# slide-8Ch-Mux-Breakout-PMODIA.net
KiCad netlist of a schematic drawn in EAGLE
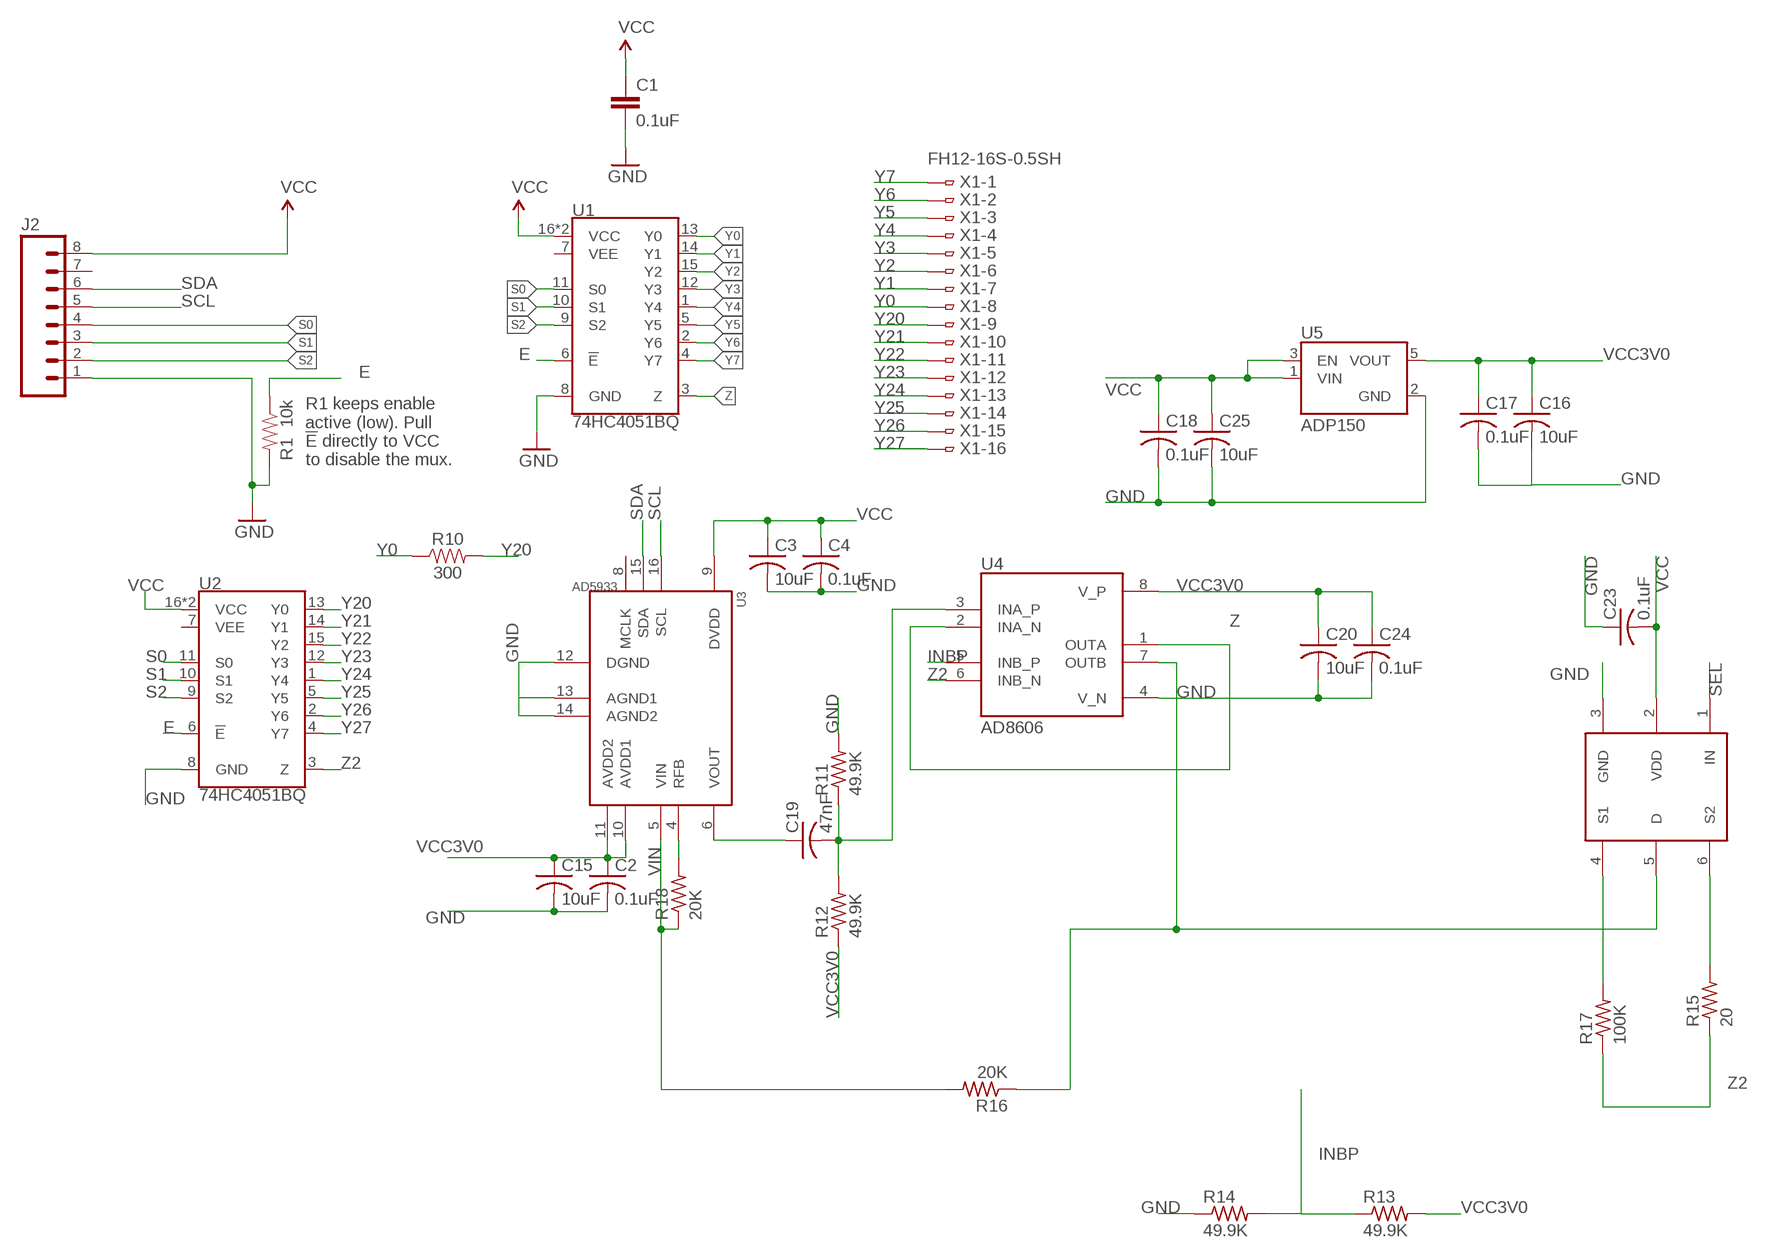
[diagram p0: schematic, sheet 1]

(export (version "E")
  (design (tool "Eeschema 10.0.6"))
  (components
    (comp (ref "C1")
      (value "0.1uF")
      (footprint "eagle-import:0603")
      (libsource (lib "eagle-import") (part "0.1UF-0603-25V-(+80/-20%)"))
    )
    (comp (ref "C2")
      (value "0.1uF")
      (footprint "eagle-import:C0805K")
      (libsource (lib "eagle-import") (part "C-USC0805K"))
    )
    (comp (ref "C3")
      (value "10uF")
      (footprint "eagle-import:C0805K")
      (libsource (lib "eagle-import") (part "C-USC0805K"))
    )
    (comp (ref "C4")
      (value "0.1uF")
      (footprint "eagle-import:C0805K")
      (libsource (lib "eagle-import") (part "C-USC0805K"))
    )
    (comp (ref "C15")
      (value "10uF")
      (footprint "eagle-import:C0805K")
      (libsource (lib "eagle-import") (part "C-USC0805K"))
    )
    (comp (ref "C16")
      (value "10uF")
      (footprint "eagle-import:C0805K")
      (libsource (lib "eagle-import") (part "C-USC0805K"))
    )
    (comp (ref "C17")
      (value "0.1uF")
      (footprint "eagle-import:C0805K")
      (libsource (lib "eagle-import") (part "C-USC0805K"))
    )
    (comp (ref "C18")
      (value "0.1uF")
      (footprint "eagle-import:C0805K")
      (libsource (lib "eagle-import") (part "C-USC0805K"))
    )
    (comp (ref "C19")
      (value "47nF")
      (footprint "eagle-import:C0805K")
      (libsource (lib "eagle-import") (part "C-USC0805K"))
    )
    (comp (ref "C20")
      (value "10uF")
      (footprint "eagle-import:C0805K")
      (libsource (lib "eagle-import") (part "C-USC0805K"))
    )
    (comp (ref "C23")
      (value "0.1uF")
      (footprint "eagle-import:C0805K")
      (libsource (lib "eagle-import") (part "C-USC0805K"))
    )
    (comp (ref "C24")
      (value "0.1uF")
      (footprint "eagle-import:C0805K")
      (libsource (lib "eagle-import") (part "C-USC0805K"))
    )
    (comp (ref "C25")
      (value "10uF")
      (footprint "eagle-import:C0805K")
      (libsource (lib "eagle-import") (part "C-USC0805K"))
    )
    (comp (ref "J2")
      (value "M08")
      (footprint "eagle-import:1X08_ROUND")
      (libsource (lib "eagle-import") (part "M08"))
    )
    (comp (ref "R1")
      (value "10k")
      (footprint "eagle-import:0603")
      (libsource (lib "eagle-import") (part "10KOHM-0603-1/10W-1%"))
    )
    (comp (ref "R10")
      (value "300")
      (footprint "eagle-import:0805")
      (libsource (lib "eagle-import") (part "0.3OHM-0805-1/8W-1%"))
    )
    (comp (ref "R11")
      (value "49.9K")
      (footprint "eagle-import:R0603")
      (libsource (lib "eagle-import") (part "R-US_R0603"))
    )
    (comp (ref "R12")
      (value "49.9K")
      (footprint "eagle-import:R0603")
      (libsource (lib "eagle-import") (part "R-US_R0603"))
    )
    (comp (ref "R13")
      (value "49.9K")
      (footprint "eagle-import:R0603")
      (libsource (lib "eagle-import") (part "R-US_R0603"))
    )
    (comp (ref "R14")
      (value "49.9K")
      (footprint "eagle-import:R0603")
      (libsource (lib "eagle-import") (part "R-US_R0603"))
    )
    (comp (ref "R15")
      (value "20")
      (footprint "eagle-import:R0603")
      (libsource (lib "eagle-import") (part "R-US_R0603"))
    )
    (comp (ref "R16")
      (value "20K")
      (footprint "eagle-import:R0603")
      (libsource (lib "eagle-import") (part "R-US_R0603"))
    )
    (comp (ref "R17")
      (value "100K")
      (footprint "eagle-import:R0603")
      (libsource (lib "eagle-import") (part "R-US_R0603"))
    )
    (comp (ref "R18")
      (value "20K")
      (footprint "eagle-import:R0603")
      (libsource (lib "eagle-import") (part "R-US_R0603"))
    )
    (comp (ref "U$1")
      (value "ADG849THROUHG_HOLE")
      (footprint "eagle-import:SOT65P210X110-6N")
      (libsource (lib "eagle-import") (part "ADG849THROUHG_HOLE"))
    )
    (comp (ref "U1")
      (value "74HC4051BQ")
      (footprint "eagle-import:DHVQFN-16-2.5X3.5MM")
      (libsource (lib "eagle-import") (part "74HC4051BQ"))
    )
    (comp (ref "U2")
      (value "74HC4051BQ")
      (footprint "eagle-import:DHVQFN-16-2.5X3.5MM")
      (libsource (lib "eagle-import") (part "74HC4051BQ"))
    )
    (comp (ref "U3")
      (value "AD5933")
      (footprint "eagle-import:SSOP16")
      (libsource (lib "eagle-import") (part "AD5933"))
    )
    (comp (ref "U4")
      (value "AD8606")
      (footprint "eagle-import:SOIC-8")
      (fields (field (name "MF") "Analog Devices") (field (name "MP") "AD8606ARZ"))
      (libsource (lib "eagle-import") (part "Updated PMODIA_AD8606"))
    )
    (comp (ref "U5")
      (value "ADP150")
      (footprint "eagle-import:SOT95P280X100-5N")
      (fields (field (name "MF") "Analog Devices") (field (name "MP") "ADP150AUJZ-2.0-R7"))
      (libsource (lib "eagle-import") (part "ADP150"))
    )
    (comp (ref "X1")
      (value "FH12-16S-0.5SH")
      (footprint "eagle-import:FH12-16S-0.5SH")
      (fields (field (name "MPN") "FH12-16S-0.5SH(55)"))
      (libsource (lib "eagle-import") (part "FH12-16S-0.5SH"))
    )
  )
  (nets
    (net (code "1") (name "/E") (class "Default")
      (node (ref "R1") (pin "1") (pinfunction "1_1") (pintype "passive"))
      (node (ref "U1") (pin "6") (pinfunction "~{E}_6") (pintype "bidirectional"))
      (node (ref "U2") (pin "6") (pinfunction "~{E}_6") (pintype "bidirectional"))
    )
    (net (code "2") (name "/INBP") (class "Default")
      (node (ref "R13") (pin "1") (pinfunction "1_1") (pintype "passive"))
      (node (ref "R14") (pin "2") (pinfunction "2_2") (pintype "passive"))
      (node (ref "U4") (pin "5") (pinfunction "INB_P_5") (pintype "input"))
    )
    (net (code "3") (name "/SCL") (class "Default")
      (node (ref "J2") (pin "5") (pinfunction "5_5") (pintype "passive"))
      (node (ref "U3") (pin "16") (pinfunction "SCL_16") (pintype "bidirectional"))
    )
    (net (code "4") (name "/SDA") (class "Default")
      (node (ref "J2") (pin "6") (pinfunction "6_6") (pintype "passive"))
      (node (ref "U3") (pin "15") (pinfunction "SDA_15") (pintype "bidirectional"))
    )
    (net (code "5") (name "/SEL") (class "Default")
      (node (ref "U$1") (pin "1") (pinfunction "IN_1") (pintype "bidirectional"))
    )
    (net (code "6") (name "/VCC3V0") (class "Default")
      (node (ref "C15") (pin "1") (pinfunction "1_1") (pintype "passive"))
      (node (ref "C16") (pin "1") (pinfunction "1_1") (pintype "passive"))
      (node (ref "C17") (pin "1") (pinfunction "1_1") (pintype "passive"))
      (node (ref "C2") (pin "1") (pinfunction "1_1") (pintype "passive"))
      (node (ref "C20") (pin "1") (pinfunction "1_1") (pintype "passive"))
      (node (ref "C24") (pin "1") (pinfunction "1_1") (pintype "passive"))
      (node (ref "R12") (pin "1") (pinfunction "1_1") (pintype "passive"))
      (node (ref "R13") (pin "2") (pinfunction "2_2") (pintype "passive"))
      (node (ref "U3") (pin "10") (pinfunction "AVDD1_10") (pintype "bidirectional"))
      (node (ref "U3") (pin "11") (pinfunction "AVDD2_11") (pintype "bidirectional"))
      (node (ref "U4") (pin "8") (pinfunction "V_P_8") (pintype "power_in"))
      (node (ref "U5") (pin "5") (pinfunction "VOUT_5") (pintype "output"))
    )
    (net (code "7") (name "/VIN") (class "Default")
      (node (ref "R16") (pin "2") (pinfunction "2_2") (pintype "passive"))
      (node (ref "R18") (pin "1") (pinfunction "1_1") (pintype "passive"))
      (node (ref "U3") (pin "5") (pinfunction "VIN_5") (pintype "bidirectional"))
    )
    (net (code "8") (name "/Y20") (class "Default")
      (node (ref "R10") (pin "2") (pinfunction "2_2") (pintype "passive"))
      (node (ref "U2") (pin "13") (pinfunction "Y0_13") (pintype "bidirectional"))
      (node (ref "X1") (pin "9") (pinfunction "1_9") (pintype "passive"))
    )
    (net (code "9") (name "/Y21") (class "Default")
      (node (ref "U2") (pin "14") (pinfunction "Y1_14") (pintype "bidirectional"))
      (node (ref "X1") (pin "10") (pinfunction "1_10") (pintype "passive"))
    )
    (net (code "10") (name "/Y22") (class "Default")
      (node (ref "U2") (pin "15") (pinfunction "Y2_15") (pintype "bidirectional"))
      (node (ref "X1") (pin "11") (pinfunction "1_11") (pintype "passive"))
    )
    (net (code "11") (name "/Y23") (class "Default")
      (node (ref "U2") (pin "12") (pinfunction "Y3_12") (pintype "bidirectional"))
      (node (ref "X1") (pin "12") (pinfunction "1_12") (pintype "passive"))
    )
    (net (code "12") (name "/Y24") (class "Default")
      (node (ref "U2") (pin "1") (pinfunction "Y4_1") (pintype "bidirectional"))
      (node (ref "X1") (pin "13") (pinfunction "1_13") (pintype "passive"))
    )
    (net (code "13") (name "/Y25") (class "Default")
      (node (ref "U2") (pin "5") (pinfunction "Y5_5") (pintype "bidirectional"))
      (node (ref "X1") (pin "14") (pinfunction "1_14") (pintype "passive"))
    )
    (net (code "14") (name "/Y26") (class "Default")
      (node (ref "U2") (pin "2") (pinfunction "Y6_2") (pintype "bidirectional"))
      (node (ref "X1") (pin "15") (pinfunction "1_15") (pintype "passive"))
    )
    (net (code "15") (name "/Y27") (class "Default")
      (node (ref "U2") (pin "4") (pinfunction "Y7_4") (pintype "bidirectional"))
      (node (ref "X1") (pin "16") (pinfunction "1_16") (pintype "passive"))
    )
    (net (code "16") (name "/Z2") (class "Default")
      (node (ref "R15") (pin "1") (pinfunction "1_1") (pintype "passive"))
      (node (ref "R17") (pin "1") (pinfunction "1_1") (pintype "passive"))
      (node (ref "U2") (pin "3") (pinfunction "Z_3") (pintype "bidirectional"))
      (node (ref "U4") (pin "6") (pinfunction "INB_N_6") (pintype "input"))
    )
    (net (code "17") (name "GND") (class "Default")
      (node (ref "C1") (pin "2") (pinfunction "2_2") (pintype "passive"))
      (node (ref "C15") (pin "2") (pinfunction "2_2") (pintype "passive"))
      (node (ref "C16") (pin "2") (pinfunction "2_2") (pintype "passive"))
      (node (ref "C17") (pin "2") (pinfunction "2_2") (pintype "passive"))
      (node (ref "C18") (pin "2") (pinfunction "2_2") (pintype "passive"))
      (node (ref "C2") (pin "2") (pinfunction "2_2") (pintype "passive"))
      (node (ref "C20") (pin "2") (pinfunction "2_2") (pintype "passive"))
      (node (ref "C23") (pin "1") (pinfunction "1_1") (pintype "passive"))
      (node (ref "C24") (pin "2") (pinfunction "2_2") (pintype "passive"))
      (node (ref "C25") (pin "2") (pinfunction "2_2") (pintype "passive"))
      (node (ref "C3") (pin "2") (pinfunction "2_2") (pintype "passive"))
      (node (ref "C4") (pin "2") (pinfunction "2_2") (pintype "passive"))
      (node (ref "J2") (pin "1") (pinfunction "1_1") (pintype "passive"))
      (node (ref "R1") (pin "2") (pinfunction "2_2") (pintype "passive"))
      (node (ref "R11") (pin "2") (pinfunction "2_2") (pintype "passive"))
      (node (ref "R14") (pin "1") (pinfunction "1_1") (pintype "passive"))
      (node (ref "U$1") (pin "3") (pinfunction "GND_3") (pintype "bidirectional"))
      (node (ref "U1") (pin "8") (pinfunction "GND_8") (pintype "bidirectional"))
      (node (ref "U2") (pin "8") (pinfunction "GND_8") (pintype "bidirectional"))
      (node (ref "U3") (pin "12") (pinfunction "DGND_12") (pintype "bidirectional"))
      (node (ref "U3") (pin "14") (pinfunction "AGND2_14") (pintype "bidirectional"))
      (node (ref "U4") (pin "4") (pinfunction "V_N_4") (pintype "power_in"))
      (node (ref "U5") (pin "2") (pinfunction "GND_2") (pintype "power_in"))
    )
    (net (code "18") (name "Net-(U$1-D)") (class "Default")
      (node (ref "R16") (pin "1") (pinfunction "1_1") (pintype "passive"))
      (node (ref "U$1") (pin "5") (pinfunction "D_5") (pintype "bidirectional"))
      (node (ref "U4") (pin "7") (pinfunction "OUTB_7") (pintype "input"))
    )
    (net (code "19") (name "Net-(U$1-S1)") (class "Default")
      (node (ref "R17") (pin "2") (pinfunction "2_2") (pintype "passive"))
      (node (ref "U$1") (pin "4") (pinfunction "S1_4") (pintype "bidirectional"))
    )
    (net (code "20") (name "Net-(U$1-S2)") (class "Default")
      (node (ref "R15") (pin "2") (pinfunction "2_2") (pintype "passive"))
      (node (ref "U$1") (pin "6") (pinfunction "S2_6") (pintype "bidirectional"))
    )
    (net (code "21") (name "Net-(U3-RFB)") (class "Default")
      (node (ref "R18") (pin "2") (pinfunction "2_2") (pintype "passive"))
      (node (ref "U3") (pin "4") (pinfunction "RFB_4") (pintype "bidirectional"))
    )
    (net (code "22") (name "Net-(U3-VOUT)") (class "Default")
      (node (ref "C19") (pin "1") (pinfunction "1_1") (pintype "passive"))
      (node (ref "U3") (pin "6") (pinfunction "VOUT_6") (pintype "bidirectional"))
    )
    (net (code "23") (name "Net-(U4-INA_P)") (class "Default")
      (node (ref "C19") (pin "2") (pinfunction "2_2") (pintype "passive"))
      (node (ref "R11") (pin "1") (pinfunction "1_1") (pintype "passive"))
      (node (ref "R12") (pin "2") (pinfunction "2_2") (pintype "passive"))
      (node (ref "U4") (pin "3") (pinfunction "INA_P_3") (pintype "input"))
    )
    (net (code "24") (name "S0") (class "Default")
      (node (ref "J2") (pin "4") (pinfunction "4_4") (pintype "passive"))
      (node (ref "U1") (pin "11") (pinfunction "S0_11") (pintype "bidirectional"))
      (node (ref "U2") (pin "11") (pinfunction "S0_11") (pintype "bidirectional"))
    )
    (net (code "25") (name "S1") (class "Default")
      (node (ref "J2") (pin "3") (pinfunction "3_3") (pintype "passive"))
      (node (ref "U1") (pin "10") (pinfunction "S1_10") (pintype "bidirectional"))
      (node (ref "U2") (pin "10") (pinfunction "S1_10") (pintype "bidirectional"))
    )
    (net (code "26") (name "S2") (class "Default")
      (node (ref "J2") (pin "2") (pinfunction "2_2") (pintype "passive"))
      (node (ref "U1") (pin "9") (pinfunction "S2_9") (pintype "bidirectional"))
      (node (ref "U2") (pin "9") (pinfunction "S2_9") (pintype "bidirectional"))
    )
    (net (code "27") (name "VCC") (class "Default")
      (node (ref "C1") (pin "1") (pinfunction "1_1") (pintype "passive"))
      (node (ref "C18") (pin "1") (pinfunction "1_1") (pintype "passive"))
      (node (ref "C23") (pin "2") (pinfunction "2_2") (pintype "passive"))
      (node (ref "C25") (pin "1") (pinfunction "1_1") (pintype "passive"))
      (node (ref "C3") (pin "1") (pinfunction "1_1") (pintype "passive"))
      (node (ref "C4") (pin "1") (pinfunction "1_1") (pintype "passive"))
      (node (ref "J2") (pin "8") (pinfunction "8_8") (pintype "passive"))
      (node (ref "U$1") (pin "2") (pinfunction "VDD_2") (pintype "bidirectional"))
      (node (ref "U1") (pin "16") (pinfunction "VCC_16") (pintype "bidirectional"))
      (node (ref "U1") (pin "EP") (pinfunction "VCC_EP") (pintype "bidirectional"))
      (node (ref "U2") (pin "16") (pinfunction "VCC_16") (pintype "bidirectional"))
      (node (ref "U2") (pin "EP") (pinfunction "VCC_EP") (pintype "bidirectional"))
      (node (ref "U3") (pin "9") (pinfunction "DVDD_9") (pintype "bidirectional"))
      (node (ref "U5") (pin "1") (pinfunction "VIN_1") (pintype "input"))
      (node (ref "U5") (pin "3") (pinfunction "EN_3") (pintype "input"))
    )
    (net (code "28") (name "Y0") (class "Default")
      (node (ref "R10") (pin "1") (pinfunction "1_1") (pintype "passive"))
      (node (ref "U1") (pin "13") (pinfunction "Y0_13") (pintype "bidirectional"))
      (node (ref "X1") (pin "8") (pinfunction "1_8") (pintype "passive"))
    )
    (net (code "29") (name "Y1") (class "Default")
      (node (ref "U1") (pin "14") (pinfunction "Y1_14") (pintype "bidirectional"))
      (node (ref "X1") (pin "7") (pinfunction "1_7") (pintype "passive"))
    )
    (net (code "30") (name "Y2") (class "Default")
      (node (ref "U1") (pin "15") (pinfunction "Y2_15") (pintype "bidirectional"))
      (node (ref "X1") (pin "6") (pinfunction "1_6") (pintype "passive"))
    )
    (net (code "31") (name "Y3") (class "Default")
      (node (ref "U1") (pin "12") (pinfunction "Y3_12") (pintype "bidirectional"))
      (node (ref "X1") (pin "5") (pinfunction "1_5") (pintype "passive"))
    )
    (net (code "32") (name "Y4") (class "Default")
      (node (ref "U1") (pin "1") (pinfunction "Y4_1") (pintype "bidirectional"))
      (node (ref "X1") (pin "4") (pinfunction "1_4") (pintype "passive"))
    )
    (net (code "33") (name "Y5") (class "Default")
      (node (ref "U1") (pin "5") (pinfunction "Y5_5") (pintype "bidirectional"))
      (node (ref "X1") (pin "3") (pinfunction "1_3") (pintype "passive"))
    )
    (net (code "34") (name "Y6") (class "Default")
      (node (ref "U1") (pin "2") (pinfunction "Y6_2") (pintype "bidirectional"))
      (node (ref "X1") (pin "2") (pinfunction "1_2") (pintype "passive"))
    )
    (net (code "35") (name "Y7") (class "Default")
      (node (ref "U1") (pin "4") (pinfunction "Y7_4") (pintype "bidirectional"))
      (node (ref "X1") (pin "1") (pinfunction "1_1") (pintype "passive"))
    )
    (net (code "36") (name "Z") (class "Default")
      (node (ref "U1") (pin "3") (pinfunction "Z_3") (pintype "bidirectional"))
      (node (ref "U4") (pin "1") (pinfunction "OUTA_1") (pintype "input"))
      (node (ref "U4") (pin "2") (pinfunction "INA_N_2") (pintype "input"))
    )
    (net (code "37") (name "unconnected-(J2-Pad7)") (class "Default")
      (node (ref "J2") (pin "7") (pinfunction "7_7") (pintype "passive"))
    )
    (net (code "38") (name "unconnected-(U1-VEE-Pad7)") (class "Default")
      (node (ref "U1") (pin "7") (pinfunction "VEE_7") (pintype "bidirectional"))
    )
    (net (code "39") (name "unconnected-(U2-VEE-Pad7)") (class "Default")
      (node (ref "U2") (pin "7") (pinfunction "VEE_7") (pintype "bidirectional"))
    )
    (net (code "40") (name "unconnected-(U3-AGND1-Pad13)") (class "Default")
      (node (ref "U3") (pin "13") (pinfunction "AGND1_13") (pintype "bidirectional"))
    )
    (net (code "41") (name "unconnected-(U3-MCLK-Pad8)") (class "Default")
      (node (ref "U3") (pin "8") (pinfunction "MCLK_8") (pintype "bidirectional"))
    )
  )
)
